# Actuators.net
KiCad netlist of a schematic drawn in Altium Designer
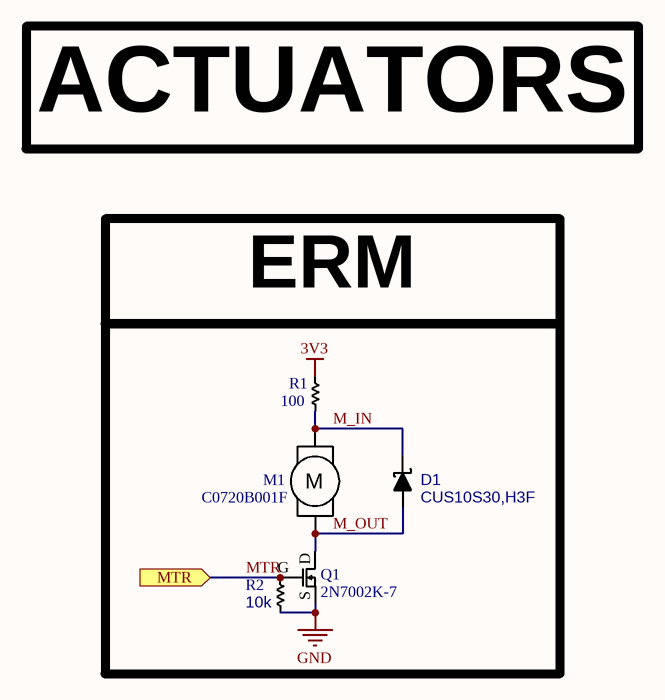
[diagram p0: Actuators.SchDoc]

(export (version "E")
  (design (tool "Eeschema 10.0.6"))
  (components
    (comp (ref "D1")
      (value "CUS10S30,H3F")
      (footprint "CUS10S30,H3F")
      (description "CUS10S30,H3F Diode Schottky 30V 1A Surface Mount USC")
      (libsource (lib "smLib") (part "CUS10S30,H3F"))
    )
    (comp (ref "M1")
      (value "C0720B001F")
      (footprint "C0720B001F")
      (description "C0720B001F DC Motor Vibration, ERM 10000 RPM   3VDC")
      (libsource (lib "smLib") (part "C0720B001F"))
    )
    (comp (ref "Q1")
      (value "2N7002K-7")
      (footprint "2N7002K-7")
      (description "2N7002K-7 MOSFET N-CH 60V 380MA SOT23-3")
      (libsource (lib "smLib") (part "2N7002K-7"))
    )
    (comp (ref "R1")
      (value "100")
      (footprint "RES_0805_HIGH")
      (description "0805 Resistor")
      (libsource (lib "smLib") (part "Resistor_0805"))
    )
    (comp (ref "R2")
      (value "10k")
      (footprint "RES_0402_HIGH")
      (description "0402 Resistor")
      (libsource (lib "smLib") (part "Resistor_0402"))
    )
  )
  (nets
    (net (code "1") (name "/MTR") (class "Default")
      (node (ref "Q1") (pin "G") (pinfunction "G_G") (pintype "passive"))
      (node (ref "R2") (pin "2") (pinfunction "2_2") (pintype "passive"))
    )
    (net (code "2") (name "/M_IN") (class "Default")
      (node (ref "D1") (pin "1") (pinfunction "1_1") (pintype "passive"))
      (node (ref "M1") (pin "2") (pinfunction "2_2") (pintype "passive"))
      (node (ref "R1") (pin "1") (pinfunction "1_1") (pintype "passive"))
    )
    (net (code "3") (name "/M_OUT") (class "Default")
      (node (ref "D1") (pin "2") (pinfunction "2_2") (pintype "passive"))
      (node (ref "M1") (pin "1") (pinfunction "1_1") (pintype "passive"))
      (node (ref "Q1") (pin "D") (pinfunction "D_D") (pintype "passive"))
    )
    (net (code "4") (name "3V3") (class "Default")
      (node (ref "R1") (pin "2") (pinfunction "2_2") (pintype "passive"))
    )
    (net (code "5") (name "GND") (class "Default")
      (node (ref "Q1") (pin "S") (pinfunction "S_S") (pintype "passive"))
      (node (ref "R2") (pin "1") (pinfunction "1_1") (pintype "passive"))
    )
  )
)
